# microcontroller.net
KiCad netlist of a schematic drawn in Altium Designer
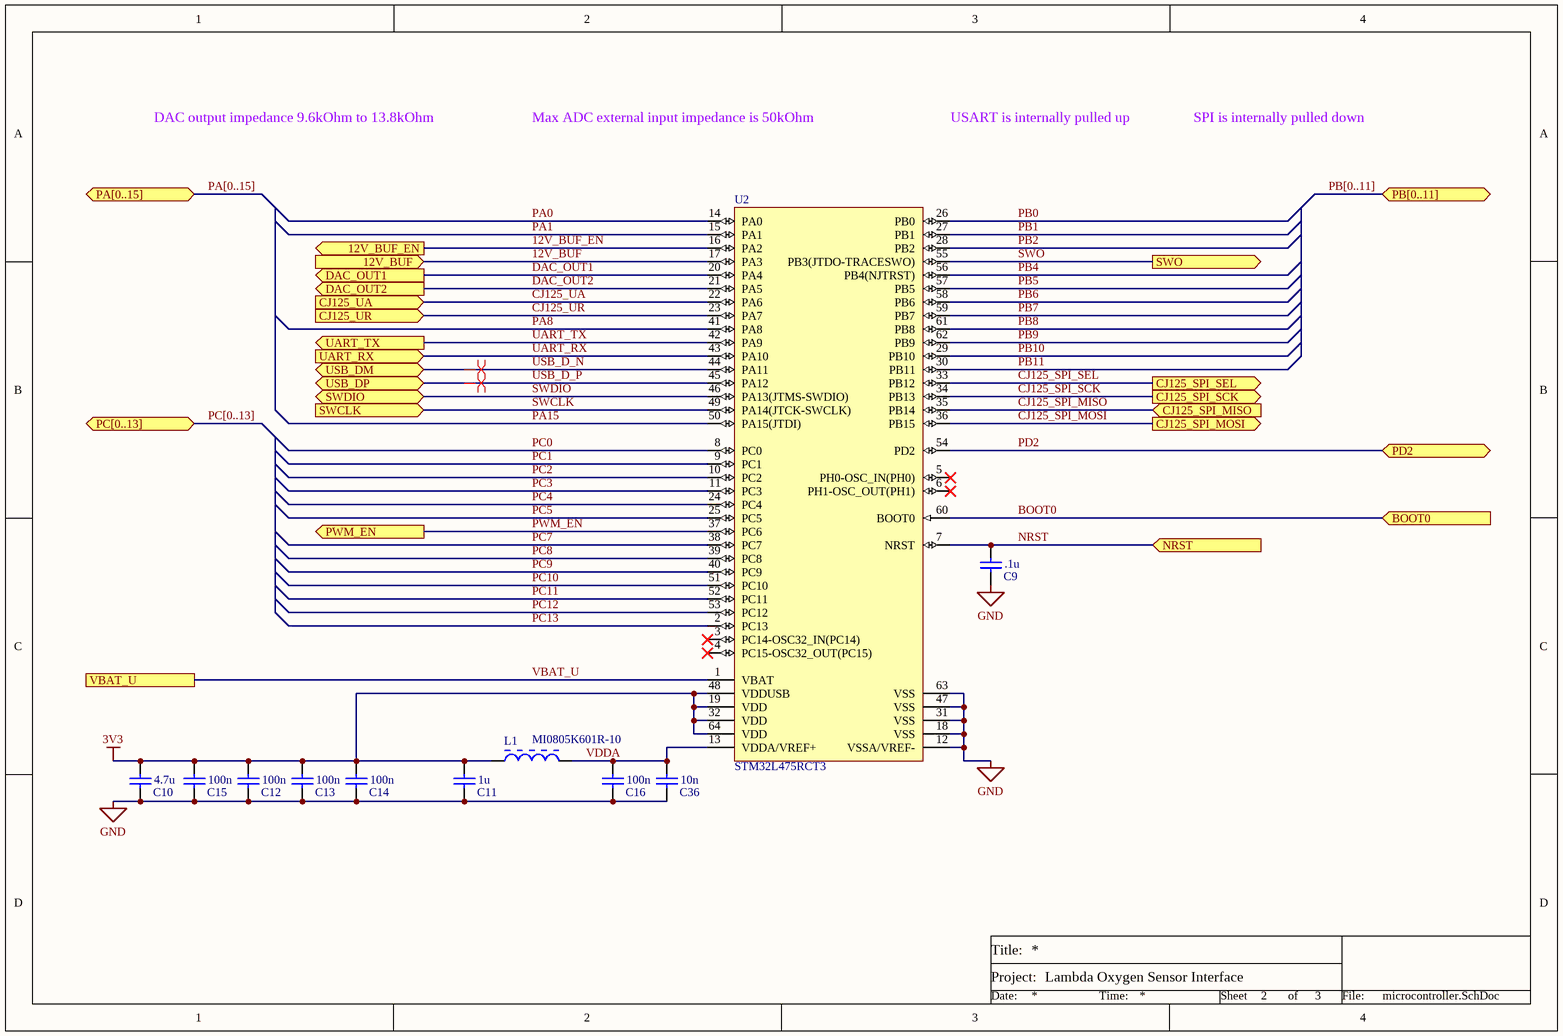
[diagram p0: microcontroller.SchDoc]

(export (version "E")
  (design (tool "Eeschema 10.0.6"))
  (components
    (comp (ref "C9")
      (value ".1u")
      (footprint "0805")
      (description "Generic 0805 Capacitor")
      (libsource (lib "symbol_library") (part "C_0805"))
    )
    (comp (ref "C10")
      (value "4.7u")
      (footprint "0805")
      (description "Generic 0805 Capacitor")
      (libsource (lib "symbol_library") (part "C_0805"))
    )
    (comp (ref "C11")
      (value "1u")
      (footprint "0805")
      (description "Generic 0805 Capacitor")
      (libsource (lib "symbol_library") (part "C_0805"))
    )
    (comp (ref "C12")
      (value "100n")
      (footprint "0805")
      (description "Generic 0805 Capacitor")
      (libsource (lib "symbol_library") (part "C_0805"))
    )
    (comp (ref "C13")
      (value "100n")
      (footprint "0805")
      (description "Generic 0805 Capacitor")
      (libsource (lib "symbol_library") (part "C_0805"))
    )
    (comp (ref "C14")
      (value "100n")
      (footprint "0805")
      (description "Generic 0805 Capacitor")
      (libsource (lib "symbol_library") (part "C_0805"))
    )
    (comp (ref "C15")
      (value "100n")
      (footprint "0805")
      (description "Generic 0805 Capacitor")
      (libsource (lib "symbol_library") (part "C_0805"))
    )
    (comp (ref "C16")
      (value "100n")
      (footprint "0805")
      (description "Generic 0805 Capacitor")
      (libsource (lib "symbol_library") (part "C_0805"))
    )
    (comp (ref "C36")
      (value "10n")
      (footprint "0805")
      (description "Generic 0805 Capacitor")
      (libsource (lib "symbol_library") (part "C_0805"))
    )
    (comp (ref "L1")
      (value "MI0805K601R-10")
      (footprint "LIRD-MI0805K601R-10-2_V")
      (fields (field (name "MANUFACTURER") "Laird"))
      (libsource (lib "symbol_library") (part "MI0805K"))
    )
    (comp (ref "U2")
      (value "STM32L475RCT3")
      (footprint "STM-LQFP64_L")
      (libsource (lib "symbol_library") (part "STM32L475RCT3"))
    )
  )
  (nets
    (net (code "15") (name "/12V_BUF") (class "Default")
      (node (ref "U2") (pin "17") (pinfunction "PA3_17") (pintype "bidirectional"))
    )
    (net (code "16") (name "/12V_BUF_EN") (class "Default")
      (node (ref "U2") (pin "16") (pinfunction "PA2_16") (pintype "bidirectional"))
    )
    (net (code "17") (name "/BOOT0") (class "Default")
      (node (ref "U2") (pin "60") (pinfunction "BOOT0_60") (pintype "input"))
    )
    (net (code "18") (name "/CJ125_SPI_MISO") (class "Default")
      (node (ref "U2") (pin "35") (pinfunction "PB14_35") (pintype "bidirectional"))
    )
    (net (code "19") (name "/CJ125_SPI_MOSI") (class "Default")
      (node (ref "U2") (pin "36") (pinfunction "PB15_36") (pintype "bidirectional"))
    )
    (net (code "20") (name "/CJ125_SPI_SCK") (class "Default")
      (node (ref "U2") (pin "34") (pinfunction "PB13_34") (pintype "bidirectional"))
    )
    (net (code "21") (name "/CJ125_SPI_SEL") (class "Default")
      (node (ref "U2") (pin "33") (pinfunction "PB12_33") (pintype "bidirectional"))
    )
    (net (code "22") (name "/CJ125_UA") (class "Default")
      (node (ref "U2") (pin "22") (pinfunction "PA6_22") (pintype "bidirectional"))
    )
    (net (code "23") (name "/CJ125_UR") (class "Default")
      (node (ref "U2") (pin "23") (pinfunction "PA7_23") (pintype "bidirectional"))
    )
    (net (code "24") (name "/DAC_OUT1") (class "Default")
      (node (ref "U2") (pin "20") (pinfunction "PA4_20") (pintype "bidirectional"))
    )
    (net (code "25") (name "/DAC_OUT2") (class "Default")
      (node (ref "U2") (pin "21") (pinfunction "PA5_21") (pintype "bidirectional"))
    )
    (net (code "26") (name "/NRST") (class "Default")
      (node (ref "C9") (pin "2") (pinfunction "2_2") (pintype "passive"))
      (node (ref "U2") (pin "7") (pinfunction "NRST_7") (pintype "bidirectional"))
    )
    (net (code "27") (name "/PA0") (class "Default")
      (node (ref "U2") (pin "14") (pinfunction "PA0_14") (pintype "bidirectional"))
    )
    (net (code "28") (name "/PA1") (class "Default")
      (node (ref "U2") (pin "15") (pinfunction "PA1_15") (pintype "bidirectional"))
    )
    (net (code "29") (name "/PA8") (class "Default")
      (node (ref "U2") (pin "41") (pinfunction "PA8_41") (pintype "bidirectional"))
    )
    (net (code "30") (name "/PA15") (class "Default")
      (node (ref "U2") (pin "50") (pinfunction "PA15(JTDI)_50") (pintype "bidirectional"))
    )
    (net (code "32") (name "/PB0") (class "Default")
      (node (ref "U2") (pin "26") (pinfunction "PB0_26") (pintype "bidirectional"))
    )
    (net (code "33") (name "/PB1") (class "Default")
      (node (ref "U2") (pin "27") (pinfunction "PB1_27") (pintype "bidirectional"))
    )
    (net (code "34") (name "/PB2") (class "Default")
      (node (ref "U2") (pin "28") (pinfunction "PB2_28") (pintype "bidirectional"))
    )
    (net (code "35") (name "/PB4") (class "Default")
      (node (ref "U2") (pin "56") (pinfunction "PB4(NJTRST)_56") (pintype "bidirectional"))
    )
    (net (code "36") (name "/PB5") (class "Default")
      (node (ref "U2") (pin "57") (pinfunction "PB5_57") (pintype "bidirectional"))
    )
    (net (code "37") (name "/PB6") (class "Default")
      (node (ref "U2") (pin "58") (pinfunction "PB6_58") (pintype "bidirectional"))
    )
    (net (code "38") (name "/PB7") (class "Default")
      (node (ref "U2") (pin "59") (pinfunction "PB7_59") (pintype "bidirectional"))
    )
    (net (code "39") (name "/PB8") (class "Default")
      (node (ref "U2") (pin "61") (pinfunction "PB8_61") (pintype "bidirectional"))
    )
    (net (code "40") (name "/PB9") (class "Default")
      (node (ref "U2") (pin "62") (pinfunction "PB9_62") (pintype "bidirectional"))
    )
    (net (code "41") (name "/PB10") (class "Default")
      (node (ref "U2") (pin "29") (pinfunction "PB10_29") (pintype "bidirectional"))
    )
    (net (code "42") (name "/PB11") (class "Default")
      (node (ref "U2") (pin "30") (pinfunction "PB11_30") (pintype "bidirectional"))
    )
    (net (code "44") (name "/PC0") (class "Default")
      (node (ref "U2") (pin "8") (pinfunction "PC0_8") (pintype "bidirectional"))
    )
    (net (code "45") (name "/PC1") (class "Default")
      (node (ref "U2") (pin "9") (pinfunction "PC1_9") (pintype "bidirectional"))
    )
    (net (code "46") (name "/PC2") (class "Default")
      (node (ref "U2") (pin "10") (pinfunction "PC2_10") (pintype "bidirectional"))
    )
    (net (code "47") (name "/PC3") (class "Default")
      (node (ref "U2") (pin "11") (pinfunction "PC3_11") (pintype "bidirectional"))
    )
    (net (code "48") (name "/PC4") (class "Default")
      (node (ref "U2") (pin "24") (pinfunction "PC4_24") (pintype "bidirectional"))
    )
    (net (code "49") (name "/PC5") (class "Default")
      (node (ref "U2") (pin "25") (pinfunction "PC5_25") (pintype "bidirectional"))
    )
    (net (code "50") (name "/PC7") (class "Default")
      (node (ref "U2") (pin "38") (pinfunction "PC7_38") (pintype "bidirectional"))
    )
    (net (code "51") (name "/PC8") (class "Default")
      (node (ref "U2") (pin "39") (pinfunction "PC8_39") (pintype "bidirectional"))
    )
    (net (code "52") (name "/PC9") (class "Default")
      (node (ref "U2") (pin "40") (pinfunction "PC9_40") (pintype "bidirectional"))
    )
    (net (code "53") (name "/PC10") (class "Default")
      (node (ref "U2") (pin "51") (pinfunction "PC10_51") (pintype "bidirectional"))
    )
    (net (code "54") (name "/PC11") (class "Default")
      (node (ref "U2") (pin "52") (pinfunction "PC11_52") (pintype "bidirectional"))
    )
    (net (code "55") (name "/PC12") (class "Default")
      (node (ref "U2") (pin "53") (pinfunction "PC12_53") (pintype "bidirectional"))
    )
    (net (code "56") (name "/PC13") (class "Default")
      (node (ref "U2") (pin "2") (pinfunction "PC13_2") (pintype "bidirectional"))
    )
    (net (code "58") (name "/PD2") (class "Default")
      (node (ref "U2") (pin "54") (pinfunction "PD2_54") (pintype "bidirectional"))
    )
    (net (code "59") (name "/PWM_EN") (class "Default")
      (node (ref "U2") (pin "37") (pinfunction "PC6_37") (pintype "bidirectional"))
    )
    (net (code "60") (name "/SWCLK") (class "Default")
      (node (ref "U2") (pin "49") (pinfunction "PA14(JTCK-SWCLK)_49") (pintype "bidirectional"))
    )
    (net (code "61") (name "/SWDIO") (class "Default")
      (node (ref "U2") (pin "46") (pinfunction "PA13(JTMS-SWDIO)_46") (pintype "bidirectional"))
    )
    (net (code "62") (name "/SWO") (class "Default")
      (node (ref "U2") (pin "55") (pinfunction "PB3(JTDO-TRACESWO)_55") (pintype "bidirectional"))
    )
    (net (code "63") (name "/UART_RX") (class "Default")
      (node (ref "U2") (pin "43") (pinfunction "PA10_43") (pintype "bidirectional"))
    )
    (net (code "64") (name "/UART_TX") (class "Default")
      (node (ref "U2") (pin "42") (pinfunction "PA9_42") (pintype "bidirectional"))
    )
    (net (code "65") (name "/USB_D_N") (class "Default")
      (node (ref "U2") (pin "44") (pinfunction "PA11_44") (pintype "bidirectional"))
    )
    (net (code "66") (name "/USB_D_P") (class "Default")
      (node (ref "U2") (pin "45") (pinfunction "PA12_45") (pintype "bidirectional"))
    )
    (net (code "67") (name "/VBAT_U") (class "Default")
      (node (ref "U2") (pin "1") (pinfunction "VBAT_1") (pintype "power_in"))
    )
    (net (code "68") (name "/VDDA") (class "Default")
      (node (ref "C16") (pin "2") (pinfunction "2_2") (pintype "passive"))
      (node (ref "C36") (pin "2") (pinfunction "2_2") (pintype "passive"))
      (node (ref "L1") (pin "2") (pinfunction "2_2") (pintype "passive"))
      (node (ref "U2") (pin "13") (pinfunction "VDDA/VREF+_13") (pintype "power_in"))
    )
    (net (code "69") (name "3V3") (class "Default")
      (node (ref "C10") (pin "2") (pinfunction "2_2") (pintype "passive"))
      (node (ref "C11") (pin "2") (pinfunction "2_2") (pintype "passive"))
      (node (ref "C12") (pin "2") (pinfunction "2_2") (pintype "passive"))
      (node (ref "C13") (pin "2") (pinfunction "2_2") (pintype "passive"))
      (node (ref "C14") (pin "2") (pinfunction "2_2") (pintype "passive"))
      (node (ref "C15") (pin "2") (pinfunction "2_2") (pintype "passive"))
      (node (ref "L1") (pin "1") (pinfunction "1_1") (pintype "passive"))
      (node (ref "U2") (pin "19") (pinfunction "VDD_19") (pintype "power_in"))
      (node (ref "U2") (pin "32") (pinfunction "VDD_32") (pintype "power_in"))
      (node (ref "U2") (pin "48") (pinfunction "VDDUSB_48") (pintype "power_in"))
      (node (ref "U2") (pin "64") (pinfunction "VDD_64") (pintype "power_in"))
    )
    (net (code "70") (name "GND") (class "Default")
      (node (ref "C10") (pin "1") (pinfunction "1_1") (pintype "passive"))
      (node (ref "C11") (pin "1") (pinfunction "1_1") (pintype "passive"))
      (node (ref "C12") (pin "1") (pinfunction "1_1") (pintype "passive"))
      (node (ref "C13") (pin "1") (pinfunction "1_1") (pintype "passive"))
      (node (ref "C14") (pin "1") (pinfunction "1_1") (pintype "passive"))
      (node (ref "C15") (pin "1") (pinfunction "1_1") (pintype "passive"))
      (node (ref "C16") (pin "1") (pinfunction "1_1") (pintype "passive"))
      (node (ref "C36") (pin "1") (pinfunction "1_1") (pintype "passive"))
      (node (ref "C9") (pin "1") (pinfunction "1_1") (pintype "passive"))
      (node (ref "U2") (pin "12") (pinfunction "VSSA/VREF-_12") (pintype "power_in"))
      (node (ref "U2") (pin "18") (pinfunction "VSS_18") (pintype "power_in"))
      (node (ref "U2") (pin "31") (pinfunction "VSS_31") (pintype "power_in"))
      (node (ref "U2") (pin "47") (pinfunction "VSS_47") (pintype "power_in"))
      (node (ref "U2") (pin "63") (pinfunction "VSS_63") (pintype "power_in"))
    )
    (net (code "71") (name "unconnected-(U2-PC14-OSC32_IN(PC14)-Pad3)") (class "Default")
      (node (ref "U2") (pin "3") (pinfunction "PC14-OSC32_IN(PC14)_3") (pintype "bidirectional+no_connect"))
    )
    (net (code "72") (name "unconnected-(U2-PC15-OSC32_OUT(PC15)-Pad4)") (class "Default")
      (node (ref "U2") (pin "4") (pinfunction "PC15-OSC32_OUT(PC15)_4") (pintype "bidirectional+no_connect"))
    )
    (net (code "73") (name "unconnected-(U2-PH0-OSC_IN(PH0)-Pad5)") (class "Default")
      (node (ref "U2") (pin "5") (pinfunction "PH0-OSC_IN(PH0)_5") (pintype "bidirectional+no_connect"))
    )
    (net (code "74") (name "unconnected-(U2-PH1-OSC_OUT(PH1)-Pad6)") (class "Default")
      (node (ref "U2") (pin "6") (pinfunction "PH1-OSC_OUT(PH1)_6") (pintype "bidirectional+no_connect"))
    )
  )
)
